# ATOL_POWER_BOARD_R02A03_20191009.net
KiCad netlist of a schematic drawn in Altium Designer
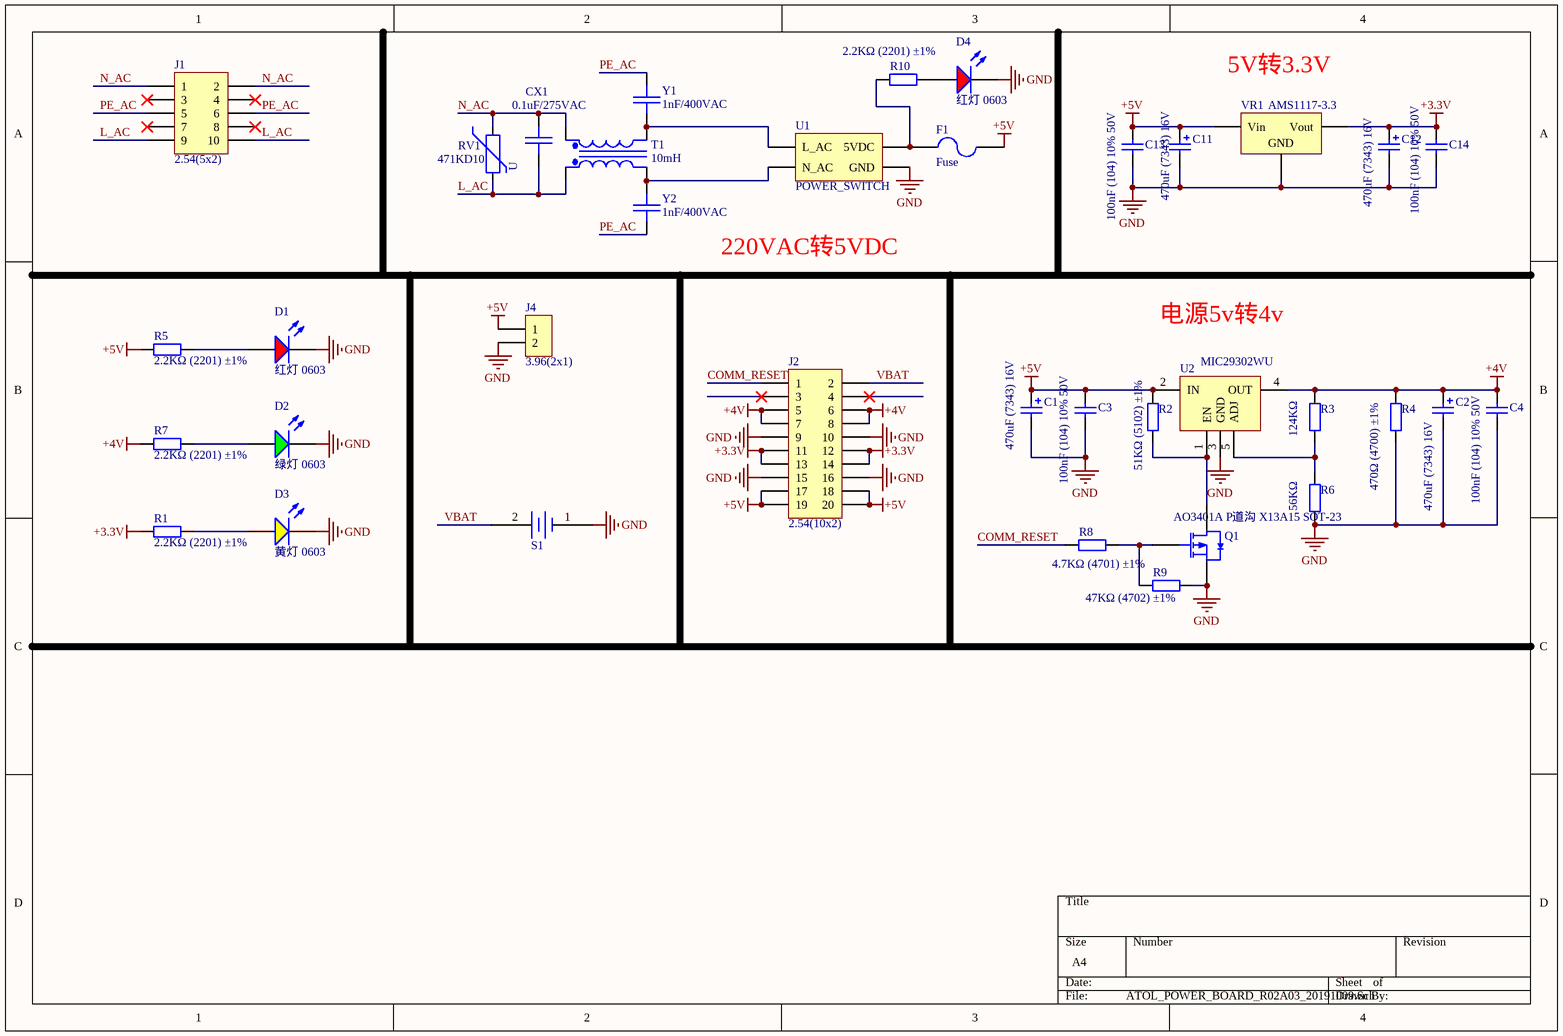
[diagram p0: ATOL_POWER_BOARD_R02A03_20191009.SchDoc]

(export (version "E")
  (design (tool "Eeschema 10.0.6"))
  (components
    (comp (ref "C1")
      (value "470uF (7343) 16V")
      (footprint "STEC_E(7343-43)")
      (description "钽电容")
      (libsource (lib "Miscellaneous Devices LC") (part "3528 100uF (107) 10% 6.3V"))
    )
    (comp (ref "C2")
      (value "470uF (7343) 16V")
      (footprint "STEC_E(7343-43)")
      (description "钽电容")
      (libsource (lib "Miscellaneous Devices LC") (part "3528 100uF (107) 10% 6.3V"))
    )
    (comp (ref "C3")
      (value "100nF (104) 10% 50V")
      (footprint "0603_C")
      (description "贴片电容")
      (libsource (lib "Miscellaneous Devices LC") (part "0603 100nF (104) 10% 50V"))
    )
    (comp (ref "C4")
      (value "100nF (104) 10% 50V")
      (footprint "0603_C")
      (description "贴片电容")
      (libsource (lib "Miscellaneous Devices LC") (part "0603 100nF (104) 10% 50V"))
    )
    (comp (ref "C11")
      (value "470uF (7343) 16V")
      (footprint "STEC_E(7343-43)")
      (description "钽电容")
      (libsource (lib "Miscellaneous Devices LC") (part "3528 100uF (107) 10% 6.3V"))
    )
    (comp (ref "C12")
      (value "470uF (7343) 16V")
      (footprint "STEC_E(7343-43)")
      (description "钽电容")
      (libsource (lib "Miscellaneous Devices LC") (part "3528 100uF (107) 10% 6.3V"))
    )
    (comp (ref "C13")
      (value "100nF (104) 10% 50V")
      (footprint "0603_C")
      (description "贴片电容")
      (libsource (lib "Miscellaneous Devices LC") (part "0603 100nF (104) 10% 50V"))
    )
    (comp (ref "C14")
      (value "100nF (104) 10% 50V")
      (footprint "0603_C")
      (description "贴片电容")
      (libsource (lib "Miscellaneous Devices LC") (part "0603 100nF (104) 10% 50V"))
    )
    (comp (ref "CX1")
      (value "0.1uF/275VAC")
      (footprint "X2-0.1U")
      (description "普通电容")
      (libsource (lib "*") (part "CAP"))
    )
    (comp (ref "D1")
      (value "红灯 0603")
      (footprint "0603_LED_S1")
      (description "发光二极管")
      (libsource (lib "Miscellaneous Devices LC") (part "0603 红灯"))
    )
    (comp (ref "D2")
      (value "绿灯 0603")
      (footprint "0603_LED_S1")
      (description "发光二极管")
      (libsource (lib "Miscellaneous Devices LC") (part "0603 绿灯"))
    )
    (comp (ref "D3")
      (value "黄灯 0603")
      (footprint "0603_LED_S1")
      (description "发光二极管")
      (libsource (lib "Miscellaneous Devices LC") (part "0603 黄灯"))
    )
    (comp (ref "D4")
      (value "红灯 0603")
      (footprint "0603_LED_S1")
      (description "发光二极管")
      (libsource (lib "Miscellaneous Devices LC") (part "0603 红灯"))
    )
    (comp (ref "F1")
      (value "Fuse")
      (footprint "1206R")
      (description "保险丝")
      (fields (field (name "PUBLISHER") "Altium Limited"))
      (libsource (lib "ATOL_CHIP") (part "Fuse"))
    )
    (comp (ref "J1")
      (value "2.54(5x2)")
      (footprint "DB2.54(5x2)")
      (description "2.54端子")
      (libsource (lib "connector") (part "2.54(5x2)"))
    )
    (comp (ref "J2")
      (value "2.54(10x2)")
      (footprint "DB2.54(10x2)")
      (description "2.54端子")
      (libsource (lib "connector") (part "2.54(10x2)"))
    )
    (comp (ref "J4")
      (value "3.96(2x1)")
      (footprint "HT3.96-WI-2P")
      (description "3.96端子")
      (libsource (lib "connector") (part "3.96(2x1)"))
    )
    (comp (ref "Q1")
      (value "AO3401A P道沟 X13A15 SOT-23")
      (footprint "SOT-23-3L")
      (description "MOS(场效应管)")
      (libsource (lib "Miscellaneous Devices LC") (part "AO3401A P道沟 X13A15 SOT-23"))
    )
    (comp (ref "R1")
      (value "2.2KΩ (2201) ±1%")
      (footprint "0603_R")
      (description "贴片电阻")
      (libsource (lib "Miscellaneous Devices LC") (part "0603 2.2KΩ (2201) 1%"))
    )
    (comp (ref "R2")
      (value "51KΩ (5102) ±1%")
      (footprint "0603_R")
      (description "贴片电阻")
      (libsource (lib "Miscellaneous Devices LC") (part "0603 51KΩ (5102) 1%"))
    )
    (comp (ref "R3")
      (value "124KΩ")
      (footprint "0603_R")
      (description "贴片电阻")
      (libsource (lib "Miscellaneous Devices LC") (part "0603 51KΩ (5102) 1%"))
    )
    (comp (ref "R4")
      (value "470Ω (4700) ±1%")
      (footprint "0603_R")
      (description "贴片电阻")
      (libsource (lib "Miscellaneous Devices LC") (part "0603 470Ω (4700) 1%"))
    )
    (comp (ref "R5")
      (value "2.2KΩ (2201) ±1%")
      (footprint "0603_R")
      (description "贴片电阻")
      (libsource (lib "Miscellaneous Devices LC") (part "0603 2.2KΩ (2201) 1%"))
    )
    (comp (ref "R6")
      (value "56KΩ")
      (footprint "0603_R")
      (description "贴片电阻")
      (libsource (lib "Miscellaneous Devices LC") (part "0603 51KΩ (5102) 1%"))
    )
    (comp (ref "R7")
      (value "2.2KΩ (2201) ±1%")
      (footprint "0603_R")
      (description "贴片电阻")
      (libsource (lib "Miscellaneous Devices LC") (part "0603 2.2KΩ (2201) 1%"))
    )
    (comp (ref "R8")
      (value "4.7KΩ (4701) ±1%")
      (footprint "0603_R")
      (description "贴片电阻")
      (libsource (lib "Miscellaneous Devices LC") (part "0603 4.7KΩ (4701) 1%"))
    )
    (comp (ref "R9")
      (value "47KΩ (4702) ±1%")
      (footprint "0603_R")
      (description "贴片电阻")
      (libsource (lib "Miscellaneous Devices LC") (part "0603 47KΩ (4702) 1%"))
    )
    (comp (ref "R10")
      (value "2.2KΩ (2201) ±1%")
      (footprint "0603_R")
      (description "贴片电阻")
      (libsource (lib "Miscellaneous Devices LC") (part "0603 2.2KΩ (2201) 1%"))
    )
    (comp (ref "RV1")
      (value "471KD10")
      (footprint "RV-14K")
      (description "压敏电阻")
      (libsource (lib "*") (part "MOV"))
    )
    (comp (ref "S1") (value "3V电池") (footprint "BATM-1220") (libsource (lib "ATOL_CHIP") (part "3V电池")))
    (comp (ref "T1")
      (value "10mH")
      (footprint "L-GM")
      (description "Transformer (Ideal)")
      (fields (field (name "PUBLISHER") "*"))
      (libsource (lib "*") (part "Trans Ideal"))
    )
    (comp (ref "U1")
      (value "POWER_SWITCH")
      (footprint "POWER_HILINK")
      (description "POWER_SWITCH_220VAC_5VDC")
      (libsource (lib "ATOL_CHIP") (part "POWER_SWITCH"))
    )
    (comp (ref "U2")
      (value "MIC29302WU")
      (footprint "LM2596")
      (description "POWER")
      (libsource (lib "ATOL_CHIP") (part "MIC29302WU"))
    )
    (comp (ref "VR1")
      (value "AMS1117-3.3")
      (footprint "SOT-223")
      (description "低压差线性稳压(LDO)")
      (libsource (lib "Miscellaneous Devices LC") (part "SOT-223 AMS1117-3.3"))
    )
    (comp (ref "Y1")
      (value "1nF/400VAC")
      (footprint "X2-1n")
      (description "普通电容")
      (libsource (lib "*") (part "CAP"))
    )
    (comp (ref "Y2")
      (value "1nF/400VAC")
      (footprint "X2-1n")
      (description "普通电容")
      (libsource (lib "*") (part "CAP"))
    )
  )
  (nets
    (net (code "1") (name "+3.3V") (class "Default")
      (node (ref "C12") (pin "1") (pinfunction "1_1") (pintype "passive"))
      (node (ref "C14") (pin "2") (pinfunction "2_2") (pintype "passive"))
      (node (ref "J2") (pin "11") (pinfunction "11_11") (pintype "passive"))
      (node (ref "J2") (pin "12") (pinfunction "12_12") (pintype "passive"))
      (node (ref "J2") (pin "13") (pinfunction "13_13") (pintype "passive"))
      (node (ref "J2") (pin "14") (pinfunction "14_14") (pintype "passive"))
      (node (ref "R1") (pin "1") (pinfunction "1_1") (pintype "passive"))
      (node (ref "VR1") (pin "2") (pinfunction "Vout_2") (pintype "passive"))
    )
    (net (code "2") (name "+4V") (class "Default")
      (node (ref "C2") (pin "1") (pinfunction "1_1") (pintype "passive"))
      (node (ref "C4") (pin "2") (pinfunction "2_2") (pintype "passive"))
      (node (ref "J2") (pin "5") (pinfunction "5_5") (pintype "passive"))
      (node (ref "J2") (pin "6") (pinfunction "6_6") (pintype "passive"))
      (node (ref "J2") (pin "7") (pinfunction "7_7") (pintype "passive"))
      (node (ref "J2") (pin "8") (pinfunction "8_8") (pintype "passive"))
      (node (ref "R3") (pin "2") (pinfunction "2_2") (pintype "passive"))
      (node (ref "R4") (pin "2") (pinfunction "2_2") (pintype "passive"))
      (node (ref "R7") (pin "1") (pinfunction "1_1") (pintype "passive"))
      (node (ref "U2") (pin "4") (pinfunction "OUT_4") (pintype "passive"))
    )
    (net (code "3") (name "+5V") (class "Default")
      (node (ref "C1") (pin "1") (pinfunction "1_1") (pintype "passive"))
      (node (ref "C11") (pin "1") (pinfunction "1_1") (pintype "passive"))
      (node (ref "C13") (pin "2") (pinfunction "2_2") (pintype "passive"))
      (node (ref "C3") (pin "2") (pinfunction "2_2") (pintype "passive"))
      (node (ref "F1") (pin "2") (pinfunction "2_2") (pintype "passive"))
      (node (ref "J2") (pin "17") (pinfunction "17_17") (pintype "passive"))
      (node (ref "J2") (pin "18") (pinfunction "18_18") (pintype "passive"))
      (node (ref "J2") (pin "19") (pinfunction "19_19") (pintype "passive"))
      (node (ref "J2") (pin "20") (pinfunction "20_20") (pintype "passive"))
      (node (ref "J4") (pin "1") (pinfunction "1_1") (pintype "passive"))
      (node (ref "R2") (pin "2") (pinfunction "2_2") (pintype "passive"))
      (node (ref "R5") (pin "1") (pinfunction "1_1") (pintype "passive"))
      (node (ref "U2") (pin "2") (pinfunction "IN_2") (pintype "passive"))
      (node (ref "VR1") (pin "3") (pinfunction "Vin_3") (pintype "passive"))
    )
    (net (code "5") (name "/COMM_RESET") (class "Default")
      (node (ref "J2") (pin "1") (pinfunction "1_1") (pintype "passive"))
      (node (ref "R8") (pin "1") (pinfunction "1_1") (pintype "passive"))
    )
    (net (code "6") (name "/L_AC") (class "Default")
      (node (ref "CX1") (pin "1") (pintype "passive"))
      (node (ref "J1") (pin "10") (pinfunction "10_10") (pintype "passive"))
      (node (ref "J1") (pin "9") (pinfunction "9_9") (pintype "passive"))
      (node (ref "RV1") (pin "1") (pintype "passive"))
      (node (ref "T1") (pin "1") (pintype "passive"))
    )
    (net (code "7") (name "/N_AC") (class "Default")
      (node (ref "CX1") (pin "2") (pintype "passive"))
      (node (ref "J1") (pin "1") (pinfunction "1_1") (pintype "passive"))
      (node (ref "J1") (pin "2") (pinfunction "2_2") (pintype "passive"))
      (node (ref "RV1") (pin "2") (pintype "passive"))
      (node (ref "T1") (pin "3") (pintype "passive"))
    )
    (net (code "8") (name "/PE_AC") (class "Default")
      (node (ref "J1") (pin "5") (pinfunction "5_5") (pintype "passive"))
      (node (ref "J1") (pin "6") (pinfunction "6_6") (pintype "passive"))
      (node (ref "Y1") (pin "2") (pintype "passive"))
      (node (ref "Y2") (pin "2") (pintype "passive"))
    )
    (net (code "9") (name "/VBAT") (class "Default")
      (node (ref "J2") (pin "2") (pinfunction "2_2") (pintype "passive"))
      (node (ref "S1") (pin "2") (pinfunction "2_2") (pintype "passive"))
    )
    (net (code "10") (name "GND") (class "Default")
      (node (ref "C1") (pin "2") (pinfunction "2_2") (pintype "passive"))
      (node (ref "C11") (pin "2") (pinfunction "2_2") (pintype "passive"))
      (node (ref "C12") (pin "2") (pinfunction "2_2") (pintype "passive"))
      (node (ref "C13") (pin "1") (pinfunction "1_1") (pintype "passive"))
      (node (ref "C14") (pin "1") (pinfunction "1_1") (pintype "passive"))
      (node (ref "C2") (pin "2") (pinfunction "2_2") (pintype "passive"))
      (node (ref "C3") (pin "1") (pinfunction "1_1") (pintype "passive"))
      (node (ref "C4") (pin "1") (pinfunction "1_1") (pintype "passive"))
      (node (ref "D1") (pin "K") (pinfunction "K_K") (pintype "passive"))
      (node (ref "D2") (pin "K") (pinfunction "K_K") (pintype "passive"))
      (node (ref "D3") (pin "K") (pinfunction "K_K") (pintype "passive"))
      (node (ref "D4") (pin "K") (pinfunction "K_K") (pintype "passive"))
      (node (ref "J2") (pin "10") (pinfunction "10_10") (pintype "passive"))
      (node (ref "J2") (pin "15") (pinfunction "15_15") (pintype "passive"))
      (node (ref "J2") (pin "16") (pinfunction "16_16") (pintype "passive"))
      (node (ref "J2") (pin "9") (pinfunction "9_9") (pintype "passive"))
      (node (ref "J4") (pin "2") (pinfunction "2_2") (pintype "passive"))
      (node (ref "Q1") (pin "2") (pinfunction "S_2") (pintype "passive"))
      (node (ref "R4") (pin "1") (pinfunction "1_1") (pintype "passive"))
      (node (ref "R6") (pin "1") (pinfunction "1_1") (pintype "passive"))
      (node (ref "R9") (pin "2") (pinfunction "2_2") (pintype "passive"))
      (node (ref "S1") (pin "1") (pinfunction "1_1") (pintype "passive"))
      (node (ref "U1") (pin "3") (pinfunction "GND_3") (pintype "passive"))
      (node (ref "U2") (pin "3") (pinfunction "GND_3") (pintype "passive"))
      (node (ref "VR1") (pin "1") (pinfunction "GND_1") (pintype "passive"))
    )
    (net (code "11") (name "Net-(D1-PadA)") (class "Default")
      (node (ref "D1") (pin "A") (pinfunction "A_A") (pintype "passive"))
      (node (ref "R5") (pin "2") (pinfunction "2_2") (pintype "passive"))
    )
    (net (code "12") (name "Net-(D2-PadA)") (class "Default")
      (node (ref "D2") (pin "A") (pinfunction "A_A") (pintype "passive"))
      (node (ref "R7") (pin "2") (pinfunction "2_2") (pintype "passive"))
    )
    (net (code "13") (name "Net-(D3-PadA)") (class "Default")
      (node (ref "D3") (pin "A") (pinfunction "A_A") (pintype "passive"))
      (node (ref "R1") (pin "2") (pinfunction "2_2") (pintype "passive"))
    )
    (net (code "14") (name "Net-(D4-PadA)") (class "Default")
      (node (ref "D4") (pin "A") (pinfunction "A_A") (pintype "passive"))
      (node (ref "R10") (pin "2") (pinfunction "2_2") (pintype "passive"))
    )
    (net (code "15") (name "Net-(Q1-D)") (class "Default")
      (node (ref "Q1") (pin "3") (pinfunction "D_3") (pintype "passive"))
      (node (ref "R2") (pin "1") (pinfunction "1_1") (pintype "passive"))
      (node (ref "U2") (pin "1") (pinfunction "EN_1") (pintype "passive"))
    )
    (net (code "16") (name "Net-(Q1-G)") (class "Default")
      (node (ref "Q1") (pin "1") (pinfunction "G_1") (pintype "passive"))
      (node (ref "R8") (pin "2") (pinfunction "2_2") (pintype "passive"))
      (node (ref "R9") (pin "1") (pinfunction "1_1") (pintype "passive"))
    )
    (net (code "17") (name "Net-(U1-5VDC)") (class "Default")
      (node (ref "F1") (pin "1") (pinfunction "1_1") (pintype "passive"))
      (node (ref "R10") (pin "1") (pinfunction "1_1") (pintype "passive"))
      (node (ref "U1") (pin "4") (pinfunction "5VDC_4") (pintype "passive"))
    )
    (net (code "18") (name "Net-(U1-L_AC)") (class "Default")
      (node (ref "T1") (pin "4") (pintype "passive"))
      (node (ref "U1") (pin "1") (pinfunction "L_AC_1") (pintype "passive"))
      (node (ref "Y1") (pin "1") (pintype "passive"))
    )
    (net (code "19") (name "Net-(U1-N_AC)") (class "Default")
      (node (ref "T1") (pin "2") (pintype "passive"))
      (node (ref "U1") (pin "2") (pinfunction "N_AC_2") (pintype "passive"))
      (node (ref "Y2") (pin "1") (pintype "passive"))
    )
    (net (code "20") (name "Net-(U2-ADJ)") (class "Default")
      (node (ref "R3") (pin "1") (pinfunction "1_1") (pintype "passive"))
      (node (ref "R6") (pin "2") (pinfunction "2_2") (pintype "passive"))
      (node (ref "U2") (pin "5") (pinfunction "ADJ_5") (pintype "passive"))
    )
    (net (code "21") (name "unconnected-(J1-Pad3)") (class "Default")
      (node (ref "J1") (pin "3") (pinfunction "3_3") (pintype "passive+no_connect"))
    )
    (net (code "22") (name "unconnected-(J1-Pad4)") (class "Default")
      (node (ref "J1") (pin "4") (pinfunction "4_4") (pintype "passive+no_connect"))
    )
    (net (code "23") (name "unconnected-(J1-Pad7)") (class "Default")
      (node (ref "J1") (pin "7") (pinfunction "7_7") (pintype "passive+no_connect"))
    )
    (net (code "24") (name "unconnected-(J1-Pad8)") (class "Default")
      (node (ref "J1") (pin "8") (pinfunction "8_8") (pintype "passive+no_connect"))
    )
    (net (code "25") (name "unconnected-(J2-Pad3)") (class "Default")
      (node (ref "J2") (pin "3") (pinfunction "3_3") (pintype "passive+no_connect"))
    )
    (net (code "26") (name "unconnected-(J2-Pad4)") (class "Default")
      (node (ref "J2") (pin "4") (pinfunction "4_4") (pintype "passive+no_connect"))
    )
  )
)
